# Apo_Board_2017_PB.net
KiCad netlist of a schematic drawn in EAGLE
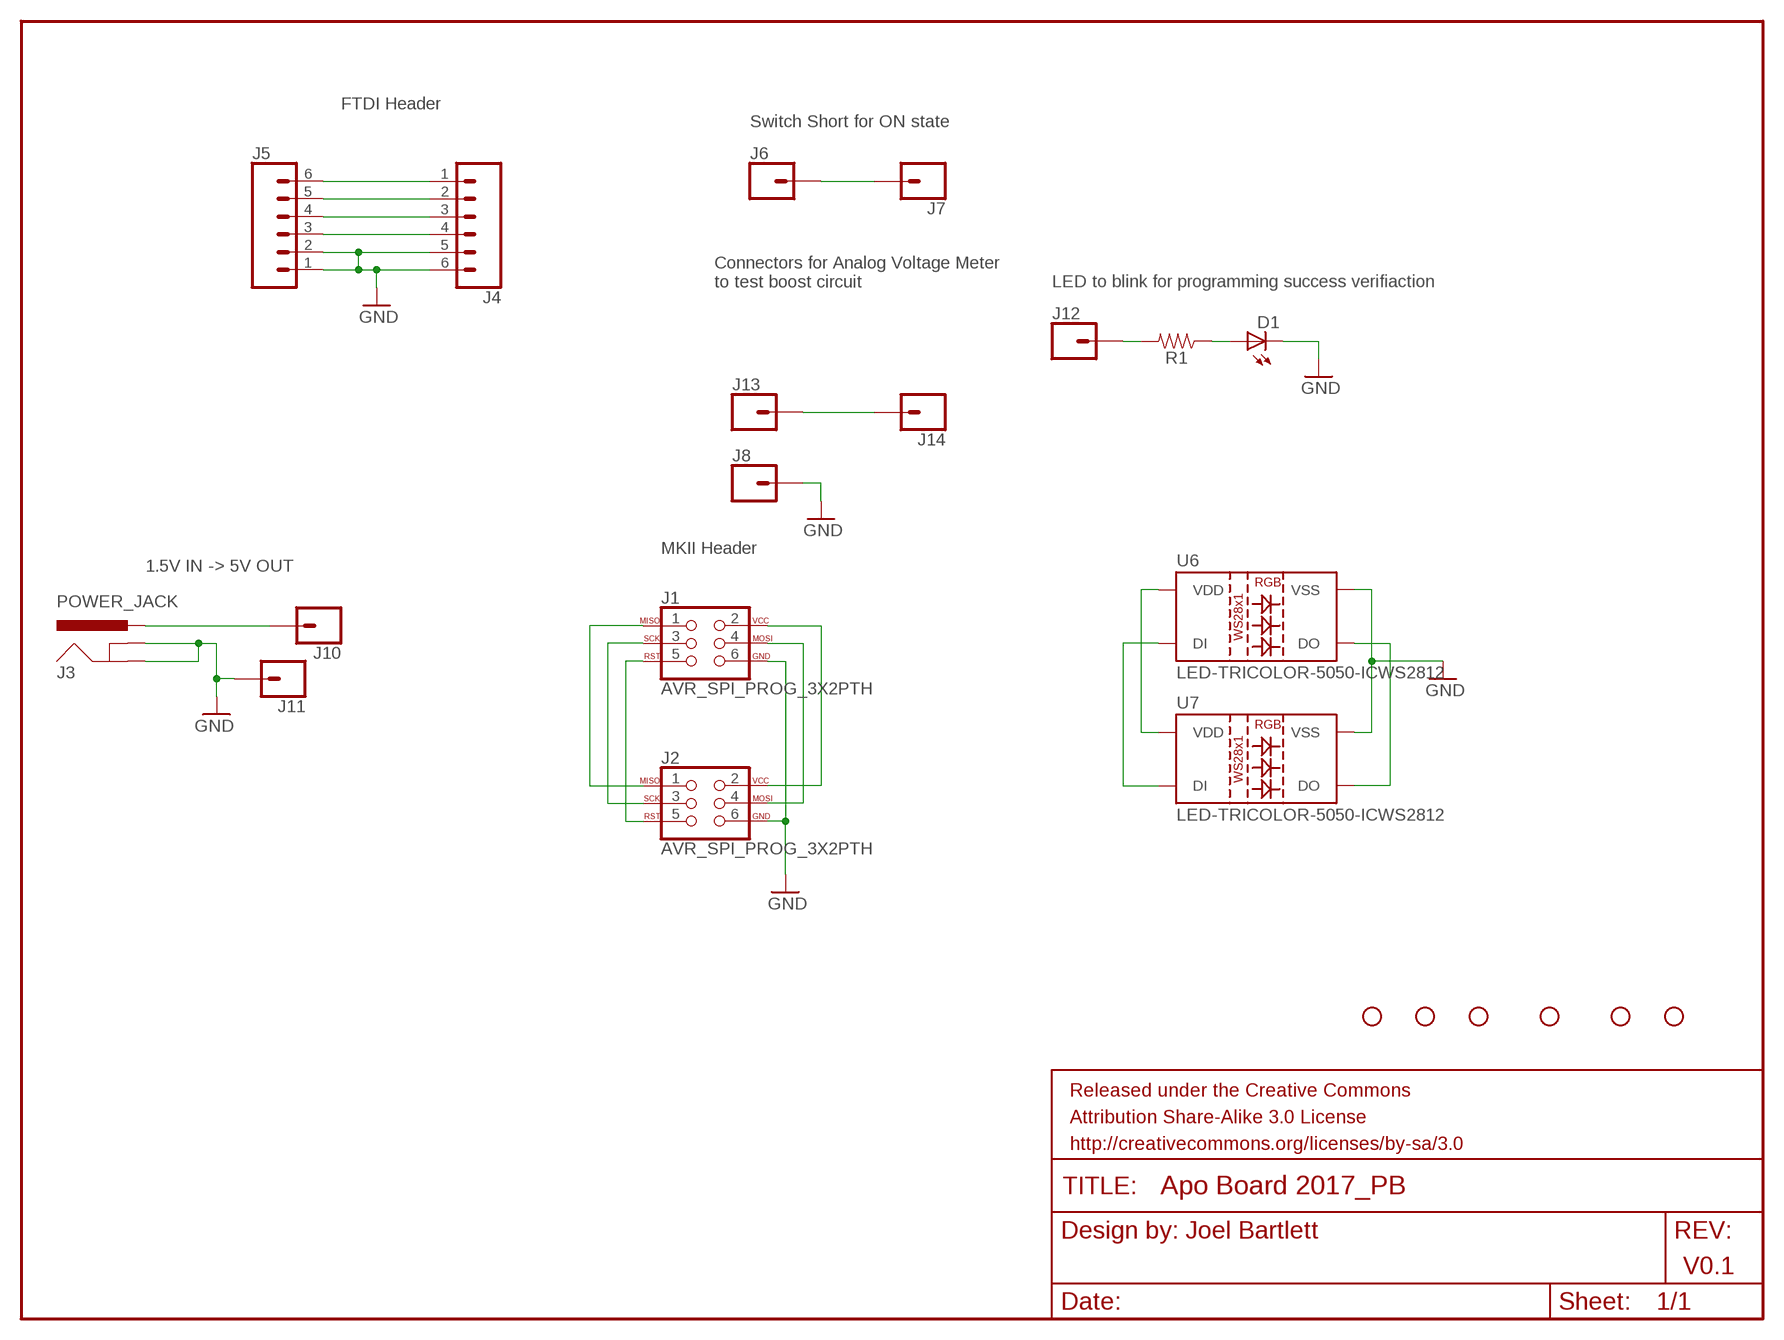
[diagram p0: schematic, sheet 1]

(export (version "E")
  (design (tool "Eeschema 10.0.6"))
  (components
    (comp (ref "D1")
      (value "LED5MM")
      (footprint "eagle-import:LED5MM")
      (libsource (lib "eagle-import") (part "LED5MM"))
    )
    (comp (ref "FRAME1")
      (value "FRAME-LETTER")
      (footprint "eagle-import:CREATIVE_COMMONS")
      (libsource (lib "eagle-import") (part "FRAME-LETTER"))
    )
    (comp (ref "H1")
      (value "STAND-OFF")
      (footprint "eagle-import:STAND-OFF")
      (libsource (lib "eagle-import") (part "STAND-OFF"))
    )
    (comp (ref "H2")
      (value "STAND-OFF")
      (footprint "eagle-import:STAND-OFF")
      (libsource (lib "eagle-import") (part "STAND-OFF"))
    )
    (comp (ref "H3")
      (value "STAND-OFF")
      (footprint "eagle-import:STAND-OFF")
      (libsource (lib "eagle-import") (part "STAND-OFF"))
    )
    (comp (ref "H4")
      (value "STAND-OFF")
      (footprint "eagle-import:STAND-OFF")
      (libsource (lib "eagle-import") (part "STAND-OFF"))
    )
    (comp (ref "H5")
      (value "STAND-OFF")
      (footprint "eagle-import:STAND-OFF")
      (libsource (lib "eagle-import") (part "STAND-OFF"))
    )
    (comp (ref "H6")
      (value "STAND-OFF")
      (footprint "eagle-import:STAND-OFF")
      (libsource (lib "eagle-import") (part "STAND-OFF"))
    )
    (comp (ref "J1")
      (value "AVR_SPI_PROG_3X2PTH")
      (footprint "eagle-import:2X3")
      (libsource (lib "eagle-import") (part "AVR_SPI_PROG_3X2PTH"))
    )
    (comp (ref "J2")
      (value "AVR_SPI_PROG_3X2PTH")
      (footprint "eagle-import:2X3")
      (libsource (lib "eagle-import") (part "AVR_SPI_PROG_3X2PTH"))
    )
    (comp (ref "J3")
      (value "POWER_JACK")
      (footprint "eagle-import:POWER_JACK_PTH")
      (libsource (lib "eagle-import") (part "POWER_JACK"))
    )
    (comp (ref "J4")
      (value "CONN_06LONGPADS")
      (footprint "eagle-import:1X06_LONGPADS")
      (libsource (lib "eagle-import") (part "CONN_06LONGPADS"))
    )
    (comp (ref "J5")
      (value "CONN_06LONGPADS")
      (footprint "eagle-import:1X06_LONGPADS")
      (libsource (lib "eagle-import") (part "CONN_06LONGPADS"))
    )
    (comp (ref "J6")
      (value "CONN_01PTH_LONGPAD")
      (footprint "eagle-import:1X01_LONGPAD")
      (libsource (lib "eagle-import") (part "CONN_01PTH_LONGPAD"))
    )
    (comp (ref "J7")
      (value "CONN_01PTH_LONGPAD")
      (footprint "eagle-import:1X01_LONGPAD")
      (libsource (lib "eagle-import") (part "CONN_01PTH_LONGPAD"))
    )
    (comp (ref "J8")
      (value "CONN_01PTH_LONGPAD")
      (footprint "eagle-import:1X01_LONGPAD")
      (libsource (lib "eagle-import") (part "CONN_01PTH_LONGPAD"))
    )
    (comp (ref "J10")
      (value "CONN_01PTH_LONGPAD")
      (footprint "eagle-import:1X01_LONGPAD")
      (libsource (lib "eagle-import") (part "CONN_01PTH_LONGPAD"))
    )
    (comp (ref "J11")
      (value "CONN_01PTH_LONGPAD")
      (footprint "eagle-import:1X01_LONGPAD")
      (libsource (lib "eagle-import") (part "CONN_01PTH_LONGPAD"))
    )
    (comp (ref "J12")
      (value "CONN_01PTH_LONGPAD")
      (footprint "eagle-import:1X01_LONGPAD")
      (libsource (lib "eagle-import") (part "CONN_01PTH_LONGPAD"))
    )
    (comp (ref "J13")
      (value "CONN_01PTH_LONGPAD")
      (footprint "eagle-import:1X01_LONGPAD")
      (libsource (lib "eagle-import") (part "CONN_01PTH_LONGPAD"))
    )
    (comp (ref "J14")
      (value "CONN_01PTH_LONGPAD")
      (footprint "eagle-import:1X01_LONGPAD")
      (libsource (lib "eagle-import") (part "CONN_01PTH_LONGPAD"))
    )
    (comp (ref "R1")
      (value "RESISTORAXIAL-0.3-KIT")
      (footprint "eagle-import:AXIAL-0.3-KIT")
      (libsource (lib "eagle-import") (part "RESISTORAXIAL-0.3-KIT"))
    )
    (comp (ref "U6")
      (value "LED-TRICOLOR-5050-ICWS2812")
      (footprint "eagle-import:LED-WS2812-THRU")
      (libsource (lib "eagle-import") (part "LED-TRICOLOR-5050-ICWS2812"))
    )
    (comp (ref "U7")
      (value "LED-TRICOLOR-5050-ICWS2812")
      (footprint "eagle-import:LED-WS2812-THRU")
      (libsource (lib "eagle-import") (part "LED-TRICOLOR-5050-ICWS2812"))
    )
  )
  (nets
    (net (code "1") (name "GND") (class "Default")
      (node (ref "D1") (pin "K") (pinfunction "C_K") (pintype "passive"))
      (node (ref "J1") (pin "6") (pinfunction "6_6") (pintype "passive"))
      (node (ref "J11") (pin "1") (pinfunction "1_1") (pintype "passive"))
      (node (ref "J2") (pin "6") (pinfunction "6_6") (pintype "passive"))
      (node (ref "J3") (pin "GND") (pinfunction "GND_GND") (pintype "bidirectional"))
      (node (ref "J3") (pin "GNDBREAK") (pinfunction "GNDBREAK_GNDBREAK") (pintype "bidirectional"))
      (node (ref "J4") (pin "5") (pinfunction "5_5") (pintype "passive"))
      (node (ref "J4") (pin "6") (pinfunction "6_6") (pintype "passive"))
      (node (ref "J5") (pin "1") (pinfunction "1_1") (pintype "passive"))
      (node (ref "J5") (pin "2") (pinfunction "2_2") (pintype "passive"))
      (node (ref "J8") (pin "1") (pinfunction "1_1") (pintype "passive"))
      (node (ref "U6") (pin "3") (pinfunction "VSS_3") (pintype "bidirectional"))
      (node (ref "U7") (pin "3") (pinfunction "VSS_3") (pintype "bidirectional"))
    )
    (net (code "2") (name "Net-(J1-Pad1)") (class "Default")
      (node (ref "J1") (pin "1") (pinfunction "1_1") (pintype "passive"))
      (node (ref "J2") (pin "1") (pinfunction "1_1") (pintype "passive"))
    )
    (net (code "3") (name "Net-(J1-Pad2)") (class "Default")
      (node (ref "J1") (pin "2") (pinfunction "2_2") (pintype "passive"))
      (node (ref "J2") (pin "2") (pinfunction "2_2") (pintype "passive"))
    )
    (net (code "4") (name "Net-(J1-Pad3)") (class "Default")
      (node (ref "J1") (pin "3") (pinfunction "3_3") (pintype "passive"))
      (node (ref "J2") (pin "3") (pinfunction "3_3") (pintype "passive"))
    )
    (net (code "5") (name "Net-(J1-Pad4)") (class "Default")
      (node (ref "J1") (pin "4") (pinfunction "4_4") (pintype "passive"))
      (node (ref "J2") (pin "4") (pinfunction "4_4") (pintype "passive"))
    )
    (net (code "6") (name "Net-(J1-Pad5)") (class "Default")
      (node (ref "J1") (pin "5") (pinfunction "5_5") (pintype "passive"))
      (node (ref "J2") (pin "5") (pinfunction "5_5") (pintype "passive"))
    )
    (net (code "7") (name "Net-(J4-Pad1)") (class "Default")
      (node (ref "J4") (pin "1") (pinfunction "1_1") (pintype "passive"))
      (node (ref "J5") (pin "6") (pinfunction "6_6") (pintype "passive"))
    )
    (net (code "8") (name "Net-(J4-Pad2)") (class "Default")
      (node (ref "J4") (pin "2") (pinfunction "2_2") (pintype "passive"))
      (node (ref "J5") (pin "5") (pinfunction "5_5") (pintype "passive"))
    )
    (net (code "9") (name "Net-(J4-Pad3)") (class "Default")
      (node (ref "J4") (pin "3") (pinfunction "3_3") (pintype "passive"))
      (node (ref "J5") (pin "4") (pinfunction "4_4") (pintype "passive"))
    )
    (net (code "10") (name "Net-(J4-Pad4)") (class "Default")
      (node (ref "J4") (pin "4") (pinfunction "4_4") (pintype "passive"))
      (node (ref "J5") (pin "3") (pinfunction "3_3") (pintype "passive"))
    )
    (net (code "11") (name "Net-(J6-Pad1)") (class "Default")
      (node (ref "J6") (pin "1") (pinfunction "1_1") (pintype "passive"))
      (node (ref "J7") (pin "1") (pinfunction "1_1") (pintype "passive"))
    )
    (net (code "12") (name "Net-(J10-Pad1)") (class "Default")
      (node (ref "J10") (pin "1") (pinfunction "1_1") (pintype "passive"))
      (node (ref "J3") (pin "PWR") (pinfunction "PWR_PWR") (pintype "bidirectional"))
    )
    (net (code "13") (name "Net-(J13-Pad1)") (class "Default")
      (node (ref "J13") (pin "1") (pinfunction "1_1") (pintype "passive"))
      (node (ref "J14") (pin "1") (pinfunction "1_1") (pintype "passive"))
    )
    (net (code "14") (name "Net-(R1-1)") (class "Default")
      (node (ref "D1") (pin "A") (pinfunction "A_A") (pintype "passive"))
      (node (ref "R1") (pin "P$1") (pinfunction "1_P$1") (pintype "passive"))
    )
    (net (code "15") (name "Net-(R1-2)") (class "Default")
      (node (ref "J12") (pin "1") (pinfunction "1_1") (pintype "passive"))
      (node (ref "R1") (pin "P$2") (pinfunction "2_P$2") (pintype "passive"))
    )
    (net (code "16") (name "Net-(U6-DI)") (class "Default")
      (node (ref "U6") (pin "1") (pinfunction "DI_1") (pintype "bidirectional"))
      (node (ref "U7") (pin "1") (pinfunction "DI_1") (pintype "bidirectional"))
    )
    (net (code "17") (name "Net-(U6-DO)") (class "Default")
      (node (ref "U6") (pin "4") (pinfunction "DO_4") (pintype "bidirectional"))
      (node (ref "U7") (pin "4") (pinfunction "DO_4") (pintype "bidirectional"))
    )
    (net (code "18") (name "Net-(U6-VDD)") (class "Default")
      (node (ref "U6") (pin "2") (pinfunction "VDD_2") (pintype "bidirectional"))
      (node (ref "U7") (pin "2") (pinfunction "VDD_2") (pintype "bidirectional"))
    )
  )
)
